# Sheet1.net
KiCad netlist of a schematic drawn in Altium Designer
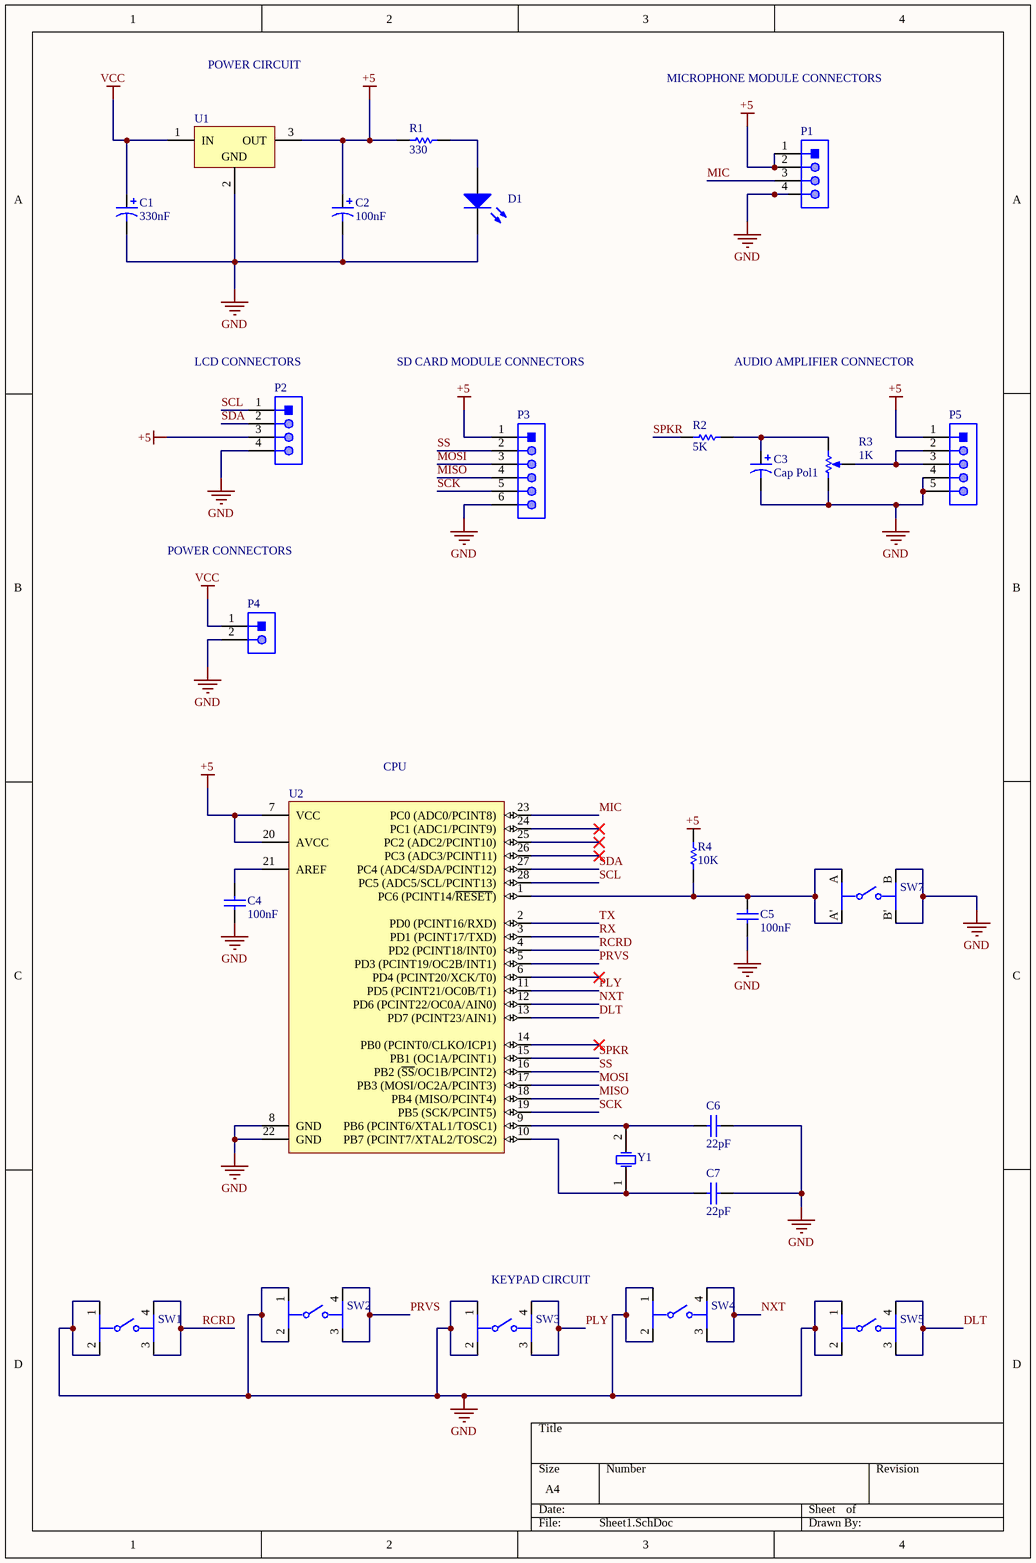
[diagram p0: Sheet1.SchDoc]

(export (version "E")
  (design (tool "Eeschema 10.0.6"))
  (components
    (comp (ref "C1")
      (value "330nF")
      (footprint "RB7.6-15")
      (description "Polarized Capacitor (Radial)")
      (fields (field (name "PUBLISHER") "Altium Limited"))
      (libsource (lib "Miscellaneous Devices") (part "Cap Pol1"))
    )
    (comp (ref "C2")
      (value "100nF")
      (footprint "RB7.6-15")
      (description "Polarized Capacitor (Radial)")
      (fields (field (name "PUBLISHER") "Altium Limited"))
      (libsource (lib "Miscellaneous Devices") (part "Cap Pol1"))
    )
    (comp (ref "C3")
      (value "Cap Pol1")
      (footprint "RB7.6-15")
      (description "Polarized Capacitor (Radial)")
      (fields (field (name "PUBLISHER") "Altium Limited"))
      (libsource (lib "Miscellaneous Devices") (part "Cap Pol1"))
    )
    (comp (ref "C4")
      (value "100nF")
      (footprint "RAD-0.3")
      (description "Capacitor")
      (fields (field (name "PUBLISHER") "Altium Limited"))
      (libsource (lib "Miscellaneous Devices") (part "Cap"))
    )
    (comp (ref "C5")
      (value "100nF")
      (footprint "RAD-0.3")
      (description "Capacitor")
      (fields (field (name "PUBLISHER") "Altium Limited"))
      (libsource (lib "Miscellaneous Devices") (part "Cap"))
    )
    (comp (ref "C6")
      (value "22pF")
      (footprint "RAD-0.3")
      (description "Capacitor")
      (fields (field (name "PUBLISHER") "Altium Limited"))
      (libsource (lib "Miscellaneous Devices") (part "Cap"))
    )
    (comp (ref "C7")
      (value "22pF")
      (footprint "RAD-0.3")
      (description "Capacitor")
      (fields (field (name "PUBLISHER") "Altium Limited"))
      (libsource (lib "Miscellaneous Devices") (part "Cap"))
    )
    (comp (ref "D1")
      (value "LED1")
      (footprint "LED-1")
      (description "Typical RED GaAs LED")
      (fields (field (name "PUBLISHER") "Altium Limited"))
      (libsource (lib "Miscellaneous Devices") (part "LED1"))
    )
    (comp (ref "P1")
      (value "620104131822")
      (footprint "620104131822")
      (description "Male Shrouded Header WR-WTB, SMT, Right Angled, pitch 2 mm, 1 x 4 position")
      (fields (field (name "MANUFACTURER") "Wurth Elektronik") (field (name "PUBLISHER") "WurthElektronik"))
      (libsource (lib "Altium Content Vault") (part "WE-CN-1P-M-R4"))
    )
    (comp (ref "P2")
      (value "620104131822")
      (footprint "620104131822")
      (description "Male Shrouded Header WR-WTB, SMT, Right Angled, pitch 2 mm, 1 x 4 position")
      (fields (field (name "MANUFACTURER") "Wurth Elektronik") (field (name "PUBLISHER") "WurthElektronik"))
      (libsource (lib "Altium Content Vault") (part "WE-CN-1P-M-R4"))
    )
    (comp (ref "P3")
      (value "66200611122")
      (footprint "66200611122")
      (description "THT Male Header WR-MPC3, Vertical, Single Row, pitch 3 mm, 6 pins")
      (fields (field (name "MANUFACTURER") "Wurth Elektronik") (field (name "PUBLISHER") "WurthElektronik"))
      (libsource (lib "Altium Content Vault") (part "WE-CN-1P-M-R6"))
    )
    (comp (ref "P4")
      (value "620302124022")
      (footprint "620302124022")
      (description "Male Shrouded Header WR-WTB, SMT, Vertical, pitch 2 mm, 1 x 2 position")
      (fields (field (name "MANUFACTURER") "Wurth Elektronik") (field (name "PUBLISHER") "WurthElektronik"))
      (libsource (lib "Altium Content Vault") (part "WE-CN-1P-M-R2"))
    )
    (comp (ref "P5")
      (value "620305124022")
      (footprint "620305124022")
      (description "Male Shrouded Header WR-WTB, SMT, Vertical, pitch 2 mm, 1 x 5 position")
      (fields (field (name "MANUFACTURER") "Wurth Elektronik") (field (name "PUBLISHER") "WurthElektronik"))
      (libsource (lib "Altium Content Vault") (part "WE-CN-1P-M-R5"))
    )
    (comp (ref "R1")
      (value "330")
      (footprint "AXIAL-0.3")
      (description "Resistor")
      (fields (field (name "PUBLISHER") "Altium Limited"))
      (libsource (lib "Miscellaneous Devices") (part "Res1"))
    )
    (comp (ref "R2")
      (value "5K")
      (footprint "AXIAL-0.3")
      (description "Resistor")
      (fields (field (name "PUBLISHER") "Altium Limited"))
      (libsource (lib "Miscellaneous Devices") (part "Res1"))
    )
    (comp (ref "R3")
      (value "1K")
      (footprint "VR5")
      (description "Potentiometer")
      (fields (field (name "PUBLISHER") "Altium Limited"))
      (libsource (lib "Miscellaneous Devices") (part "RPot"))
    )
    (comp (ref "R4")
      (value "10K")
      (footprint "AXIAL-0.3")
      (description "Resistor")
      (fields (field (name "PUBLISHER") "Altium Limited"))
      (libsource (lib "Miscellaneous Devices") (part "Res1"))
    )
    (comp (ref "SW1")
      (value "B3FS-4052P")
      (footprint "FP-B3FS-4052P-MFG")
      (description "SWITCH TACT SPST-NO 0.05A 24V")
      (libsource (lib "Altium Content Vault") (part "512b1658425e80dc09bd29e095ee4d3"))
    )
    (comp (ref "SW2")
      (value "B3FS-4052P")
      (footprint "FP-B3FS-4052P-MFG")
      (description "SWITCH TACT SPST-NO 0.05A 24V")
      (libsource (lib "Altium Content Vault") (part "512b1658425e80dc09bd29e095ee4d3"))
    )
    (comp (ref "SW3")
      (value "B3FS-4052P")
      (footprint "FP-B3FS-4052P-MFG")
      (description "SWITCH TACT SPST-NO 0.05A 24V")
      (libsource (lib "Altium Content Vault") (part "512b1658425e80dc09bd29e095ee4d3"))
    )
    (comp (ref "SW4")
      (value "B3FS-4052P")
      (footprint "FP-B3FS-4052P-MFG")
      (description "SWITCH TACT SPST-NO 0.05A 24V")
      (libsource (lib "Altium Content Vault") (part "512b1658425e80dc09bd29e095ee4d3"))
    )
    (comp (ref "SW5")
      (value "B3FS-4052P")
      (footprint "FP-B3FS-4052P-MFG")
      (description "SWITCH TACT SPST-NO 0.05A 24V")
      (libsource (lib "Altium Content Vault") (part "512b1658425e80dc09bd29e095ee4d3"))
    )
    (comp (ref "SW7")
      (value "EVQ-PAG07K")
      (footprint "FP-EVQ-PAG07K-MFG")
      (description "SWITCH TACTILE SPST-NO 0.02A 15V")
      (libsource (lib "Altium Content Vault") (part "75038bc65b1af1a6bd057da08483287"))
    )
    (comp (ref "U1")
      (value "L7805CV")
      (footprint "TO220")
      (description "Positive Voltage Regulator, 5V, 3-Pin TO-220")
      (libsource (lib "Altium Content Vault") (part "PM-REG-L4940-SIL3"))
    )
    (comp (ref "U2")
      (value "ATmega328P-PU")
      (footprint "28P3")
      (libsource (lib "Altium Content Vault") (part "MC-8B-ATM48-IL28"))
    )
    (comp (ref "Y1")
      (value "XTAL")
      (footprint "R38")
      (description "Crystal Oscillator")
      (fields (field (name "PUBLISHER") "Altium Limited"))
      (libsource (lib "Miscellaneous Devices") (part "XTAL"))
    )
  )
  (nets
    (net (code "1") (name "+5") (class "Default")
      (node (ref "C2") (pin "1") (pinfunction "1_1") (pintype "passive"))
      (node (ref "P1") (pin "1") (pinfunction "1_1") (pintype "passive"))
      (node (ref "P1") (pin "2") (pinfunction "2_2") (pintype "passive"))
      (node (ref "P2") (pin "3") (pinfunction "3_3") (pintype "passive"))
      (node (ref "P3") (pin "1") (pinfunction "1_1") (pintype "passive"))
      (node (ref "P5") (pin "1") (pinfunction "1_1") (pintype "passive"))
      (node (ref "R1") (pin "1") (pinfunction "1_1") (pintype "passive"))
      (node (ref "U1") (pin "3") (pinfunction "OUT_3") (pintype "power_in"))
      (node (ref "U2") (pin "20") (pinfunction "AVCC_20") (pintype "power_in"))
      (node (ref "U2") (pin "7") (pinfunction "VCC_7") (pintype "power_in"))
    )
    (net (code "2") (name "/DLT") (class "Default")
      (node (ref "SW5") (pin "3") (pinfunction "3_3") (pintype "passive"))
      (node (ref "SW5") (pin "4") (pinfunction "4_4") (pintype "passive"))
      (node (ref "U2") (pin "13") (pinfunction "PD7_(PCINT23/AIN1)_13") (pintype "bidirectional"))
    )
    (net (code "3") (name "/MIC") (class "Default")
      (node (ref "P1") (pin "3") (pinfunction "3_3") (pintype "passive"))
      (node (ref "U2") (pin "23") (pinfunction "PC0_(ADC0/PCINT8)_23") (pintype "bidirectional"))
    )
    (net (code "4") (name "/MISO") (class "Default")
      (node (ref "P3") (pin "4") (pinfunction "4_4") (pintype "passive"))
      (node (ref "U2") (pin "18") (pinfunction "PB4_(MISO/PCINT4)_18") (pintype "bidirectional"))
    )
    (net (code "5") (name "/MOSI") (class "Default")
      (node (ref "P3") (pin "3") (pinfunction "3_3") (pintype "passive"))
      (node (ref "U2") (pin "17") (pinfunction "PB3_(MOSI/OC2A/PCINT3)_17") (pintype "bidirectional"))
    )
    (net (code "6") (name "/NXT") (class "Default")
      (node (ref "SW4") (pin "3") (pinfunction "3_3") (pintype "passive"))
      (node (ref "SW4") (pin "4") (pinfunction "4_4") (pintype "passive"))
      (node (ref "U2") (pin "12") (pinfunction "PD6_(PCINT22/OC0A/AIN0)_12") (pintype "bidirectional"))
    )
    (net (code "7") (name "/PLY") (class "Default")
      (node (ref "SW3") (pin "3") (pinfunction "3_3") (pintype "passive"))
      (node (ref "SW3") (pin "4") (pinfunction "4_4") (pintype "passive"))
      (node (ref "U2") (pin "11") (pinfunction "PD5_(PCINT21/OC0B/T1)_11") (pintype "bidirectional"))
    )
    (net (code "8") (name "/PRVS") (class "Default")
      (node (ref "SW2") (pin "3") (pinfunction "3_3") (pintype "passive"))
      (node (ref "SW2") (pin "4") (pinfunction "4_4") (pintype "passive"))
      (node (ref "U2") (pin "5") (pinfunction "PD3_(PCINT19/OC2B/INT1)_5") (pintype "bidirectional"))
    )
    (net (code "9") (name "/RCRD") (class "Default")
      (node (ref "SW1") (pin "3") (pinfunction "3_3") (pintype "passive"))
      (node (ref "SW1") (pin "4") (pinfunction "4_4") (pintype "passive"))
      (node (ref "U2") (pin "4") (pinfunction "PD2_(PCINT18/INT0)_4") (pintype "bidirectional"))
    )
    (net (code "10") (name "/RX") (class "Default")
      (node (ref "U2") (pin "3") (pinfunction "PD1_(PCINT17/TXD)_3") (pintype "bidirectional"))
    )
    (net (code "11") (name "/SCK") (class "Default")
      (node (ref "P3") (pin "5") (pinfunction "5_5") (pintype "passive"))
      (node (ref "U2") (pin "19") (pinfunction "PB5_(SCK/PCINT5)_19") (pintype "bidirectional"))
    )
    (net (code "12") (name "/SCL") (class "Default")
      (node (ref "P2") (pin "1") (pinfunction "1_1") (pintype "passive"))
      (node (ref "U2") (pin "28") (pinfunction "PC5_(ADC5/SCL/PCINT13)_28") (pintype "bidirectional"))
    )
    (net (code "13") (name "/SDA") (class "Default")
      (node (ref "P2") (pin "2") (pinfunction "2_2") (pintype "passive"))
      (node (ref "U2") (pin "27") (pinfunction "PC4_(ADC4/SDA/PCINT12)_27") (pintype "bidirectional"))
    )
    (net (code "14") (name "/SPKR") (class "Default")
      (node (ref "R2") (pin "2") (pinfunction "2_2") (pintype "passive"))
      (node (ref "U2") (pin "15") (pinfunction "PB1_(OC1A/PCINT1)_15") (pintype "bidirectional"))
    )
    (net (code "15") (name "/SS") (class "Default")
      (node (ref "P3") (pin "2") (pinfunction "2_2") (pintype "passive"))
      (node (ref "U2") (pin "16") (pinfunction "PB2_(~{SS}/OC1B/PCINT2)_16") (pintype "bidirectional"))
    )
    (net (code "16") (name "/TX") (class "Default")
      (node (ref "U2") (pin "2") (pinfunction "PD0_(PCINT16/RXD)_2") (pintype "bidirectional"))
    )
    (net (code "17") (name "GND") (class "Default")
      (node (ref "C1") (pin "2") (pinfunction "2_2") (pintype "passive"))
      (node (ref "C2") (pin "2") (pinfunction "2_2") (pintype "passive"))
      (node (ref "C3") (pin "2") (pinfunction "2_2") (pintype "passive"))
      (node (ref "C4") (pin "1") (pinfunction "1_1") (pintype "passive"))
      (node (ref "C5") (pin "1") (pinfunction "1_1") (pintype "passive"))
      (node (ref "C6") (pin "1") (pinfunction "1_1") (pintype "passive"))
      (node (ref "C7") (pin "1") (pinfunction "1_1") (pintype "passive"))
      (node (ref "D1") (pin "2") (pinfunction "K_2") (pintype "passive"))
      (node (ref "P1") (pin "4") (pinfunction "4_4") (pintype "passive"))
      (node (ref "P2") (pin "4") (pinfunction "4_4") (pintype "passive"))
      (node (ref "P3") (pin "6") (pinfunction "6_6") (pintype "passive"))
      (node (ref "P4") (pin "2") (pinfunction "2_2") (pintype "passive"))
      (node (ref "P5") (pin "4") (pinfunction "4_4") (pintype "passive"))
      (node (ref "P5") (pin "5") (pinfunction "5_5") (pintype "passive"))
      (node (ref "R3") (pin "1") (pinfunction "TOP_1") (pintype "passive"))
      (node (ref "SW1") (pin "1") (pinfunction "1_1") (pintype "passive"))
      (node (ref "SW1") (pin "2") (pinfunction "2_2") (pintype "passive"))
      (node (ref "SW2") (pin "1") (pinfunction "1_1") (pintype "passive"))
      (node (ref "SW2") (pin "2") (pinfunction "2_2") (pintype "passive"))
      (node (ref "SW3") (pin "1") (pinfunction "1_1") (pintype "passive"))
      (node (ref "SW3") (pin "2") (pinfunction "2_2") (pintype "passive"))
      (node (ref "SW4") (pin "1") (pinfunction "1_1") (pintype "passive"))
      (node (ref "SW4") (pin "2") (pinfunction "2_2") (pintype "passive"))
      (node (ref "SW5") (pin "1") (pinfunction "1_1") (pintype "passive"))
      (node (ref "SW5") (pin "2") (pinfunction "2_2") (pintype "passive"))
      (node (ref "SW7") (pin "B") (pinfunction "B_B") (pintype "passive"))
      (node (ref "SW7") (pin "B'") (pinfunction "B'_B'") (pintype "passive"))
      (node (ref "U1") (pin "2") (pinfunction "GND_2") (pintype "power_in"))
      (node (ref "U2") (pin "22") (pinfunction "GND_22") (pintype "power_in"))
      (node (ref "U2") (pin "8") (pinfunction "GND_8") (pintype "power_in"))
    )
    (net (code "18") (name "Net-(D1-A)") (class "Default")
      (node (ref "D1") (pin "1") (pinfunction "A_1") (pintype "passive"))
      (node (ref "R1") (pin "2") (pinfunction "2_2") (pintype "passive"))
    )
    (net (code "19") (name "Net-(R3-BOT)") (class "Default")
      (node (ref "C3") (pin "1") (pinfunction "1_1") (pintype "passive"))
      (node (ref "R2") (pin "1") (pinfunction "1_1") (pintype "passive"))
      (node (ref "R3") (pin "2") (pinfunction "BOT_2") (pintype "passive"))
    )
    (net (code "20") (name "Net-(R3-TAP)") (class "Default")
      (node (ref "P5") (pin "2") (pinfunction "2_2") (pintype "passive"))
      (node (ref "P5") (pin "3") (pinfunction "3_3") (pintype "passive"))
      (node (ref "R3") (pin "3") (pinfunction "TAP_3") (pintype "passive"))
    )
    (net (code "21") (name "Net-(U2-AREF)") (class "Default")
      (node (ref "C4") (pin "2") (pinfunction "2_2") (pintype "passive"))
      (node (ref "U2") (pin "21") (pinfunction "AREF_21") (pintype "power_in"))
    )
    (net (code "22") (name "Net-(U2-PB6_(PCINT6{slash}XTAL1{slash}TOSC1))") (class "Default")
      (node (ref "C6") (pin "2") (pinfunction "2_2") (pintype "passive"))
      (node (ref "U2") (pin "9") (pinfunction "PB6_(PCINT6/XTAL1/TOSC1)_9") (pintype "bidirectional"))
      (node (ref "Y1") (pin "2") (pinfunction "OSC2_2") (pintype "passive"))
    )
    (net (code "23") (name "Net-(U2-PB7_(PCINT7{slash}XTAL2{slash}TOSC2))") (class "Default")
      (node (ref "C7") (pin "2") (pinfunction "2_2") (pintype "passive"))
      (node (ref "U2") (pin "10") (pinfunction "PB7_(PCINT7/XTAL2/TOSC2)_10") (pintype "bidirectional"))
      (node (ref "Y1") (pin "1") (pinfunction "OSC1_1") (pintype "passive"))
    )
    (net (code "24") (name "Net-(U2-PC6_(PCINT14{slash}~{RESET}))") (class "Default")
      (node (ref "C5") (pin "2") (pinfunction "2_2") (pintype "passive"))
      (node (ref "R4") (pin "2") (pinfunction "2_2") (pintype "passive"))
      (node (ref "SW7") (pin "A") (pinfunction "A_A") (pintype "passive"))
      (node (ref "SW7") (pin "A'") (pinfunction "A'_A'") (pintype "passive"))
      (node (ref "U2") (pin "1") (pinfunction "PC6_(PCINT14/~{RESET})_1") (pintype "bidirectional"))
    )
    (net (code "25") (name "VCC") (class "Default")
      (node (ref "C1") (pin "1") (pinfunction "1_1") (pintype "passive"))
      (node (ref "P4") (pin "1") (pinfunction "1_1") (pintype "passive"))
      (node (ref "U1") (pin "1") (pinfunction "IN_1") (pintype "power_in"))
    )
    (net (code "26") (name "unconnected-(R4-Pad1)") (class "Default")
      (node (ref "R4") (pin "1") (pinfunction "1_1") (pintype "passive"))
    )
    (net (code "27") (name "unconnected-(U2-PB0_(PCINT0{slash}CLKO{slash}ICP1)-Pad14)") (class "Default")
      (node (ref "U2") (pin "14") (pinfunction "PB0_(PCINT0/CLKO/ICP1)_14") (pintype "bidirectional+no_connect"))
    )
    (net (code "28") (name "unconnected-(U2-PC1_(ADC1{slash}PCINT9)-Pad24)") (class "Default")
      (node (ref "U2") (pin "24") (pinfunction "PC1_(ADC1/PCINT9)_24") (pintype "bidirectional+no_connect"))
    )
    (net (code "29") (name "unconnected-(U2-PC2_(ADC2{slash}PCINT10)-Pad25)") (class "Default")
      (node (ref "U2") (pin "25") (pinfunction "PC2_(ADC2/PCINT10)_25") (pintype "bidirectional+no_connect"))
    )
    (net (code "30") (name "unconnected-(U2-PC3_(ADC3{slash}PCINT11)-Pad26)") (class "Default")
      (node (ref "U2") (pin "26") (pinfunction "PC3_(ADC3/PCINT11)_26") (pintype "bidirectional+no_connect"))
    )
    (net (code "31") (name "unconnected-(U2-PD4_(PCINT20{slash}XCK{slash}T0)-Pad6)") (class "Default")
      (node (ref "U2") (pin "6") (pinfunction "PD4_(PCINT20/XCK/T0)_6") (pintype "bidirectional+no_connect"))
    )
  )
)
